# On-Off_Signal_Control.net
KiCad netlist of a schematic drawn in Altium Designer
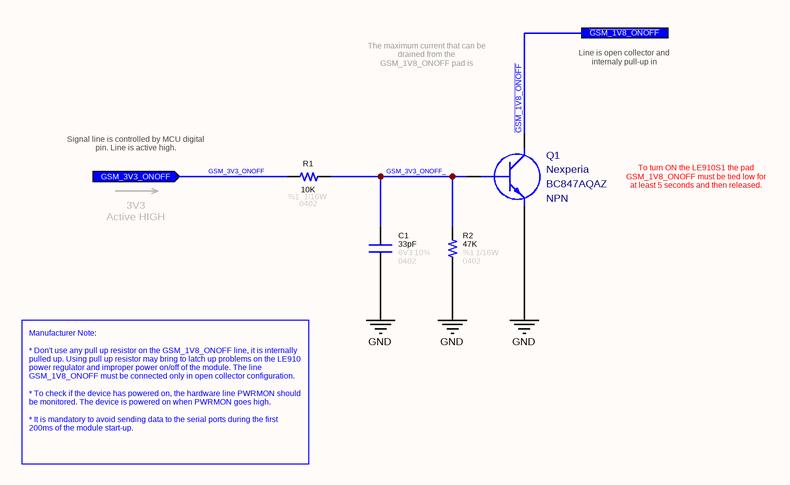
[diagram p0: On-Off Signal Control.SchDoc]

(export (version "E")
  (design (tool "Eeschema 10.0.6"))
  (components
    (comp (ref "C1")
      (value "33pF")
      (footprint "CAPACITOR_0402")
      (description "Capacitor - 33pF [0402] (Ceramic)")
      (fields
        (field (name "MANUFACTURER PART NUMBER") "C0402C330J9RACAUTO")
        (field (name "TOLERANCE") "10%")
        (field (name "CASE") "0402")
        (field (name "VOLTAGE") "6V3")
      )
      (libsource (lib "P101DA_Library") (part "Capacitor - 33pF [0402-6V3]"))
    )
    (comp (ref "Q1")
      (value "BC847AQAZ")
      (footprint "SOT1215")
      (description "Bipolar NPN Transistors")
      (fields
        (field (name "MANUFACTURER NAME") "Nexperia")
        (field (name "MANUFACTURER PART NUMBER") "BC847AQAZ")
        (field (name "POLARITY") "NPN")
      )
      (libsource (lib "P101DA_Library") (part "Transistor - BC847"))
    )
    (comp (ref "R1")
      (value "10K")
      (footprint "RESISTOR_0402")
      (description "Thick Film Resistors - SMD 1/16 W 10 KOhm 1%")
      (fields
        (field (name "MANUFACTURER PART NUMBER") "CRCW040210K0FKED")
        (field (name "TOLERANCE") "%1")
        (field (name "CASE") "0402")
        (field (name "POWER") "1/16W")
        (field (name "Comment") "10K - 0402 - %1 - 1/16W")
      )
      (libsource (lib "P101DA_Library") (part "Resistor - 10K [0402]"))
    )
    (comp (ref "R2")
      (value "47K")
      (footprint "RESISTOR_0402")
      (description "Thick Film Resistors - SMD 1/16 W 47 KOhm 1%")
      (fields
        (field (name "MANUFACTURER PART NUMBER") "CRCW040247K0FKED")
        (field (name "TOLERANCE") "%1")
        (field (name "CASE") "0402")
        (field (name "POWER") "1/16W")
        (field (name "Comment") "47K - 0402 - %1 - 1/16W")
      )
      (libsource (lib "P101DA_Library") (part "Resistor - 47K [0402]"))
    )
  )
  (nets
    (net (code "1") (name "/GSM_3V3_ONOFF") (class "Default")
      (node (ref "R1") (pin "2") (pinfunction "2_2") (pintype "passive"))
    )
    (net (code "2") (name "/GSM_3V3_ONOFF_") (class "Default")
      (node (ref "C1") (pin "2") (pinfunction "2_2") (pintype "passive"))
      (node (ref "Q1") (pin "1") (pinfunction "B_1") (pintype "passive"))
      (node (ref "R1") (pin "1") (pinfunction "1_1") (pintype "passive"))
      (node (ref "R2") (pin "2") (pinfunction "2_2") (pintype "passive"))
    )
    (net (code "3") (name "/~{GSM_1V8_ONOFF}") (class "Default")
      (node (ref "Q1") (pin "3") (pinfunction "C_3") (pintype "passive"))
    )
    (net (code "4") (name "GND") (class "Default")
      (node (ref "C1") (pin "1") (pinfunction "1_1") (pintype "passive"))
      (node (ref "Q1") (pin "2") (pinfunction "E_2") (pintype "passive"))
      (node (ref "R2") (pin "1") (pinfunction "1_1") (pintype "passive"))
    )
  )
)
